# I2C_MB.net
KiCad netlist of a schematic drawn in Altium Designer
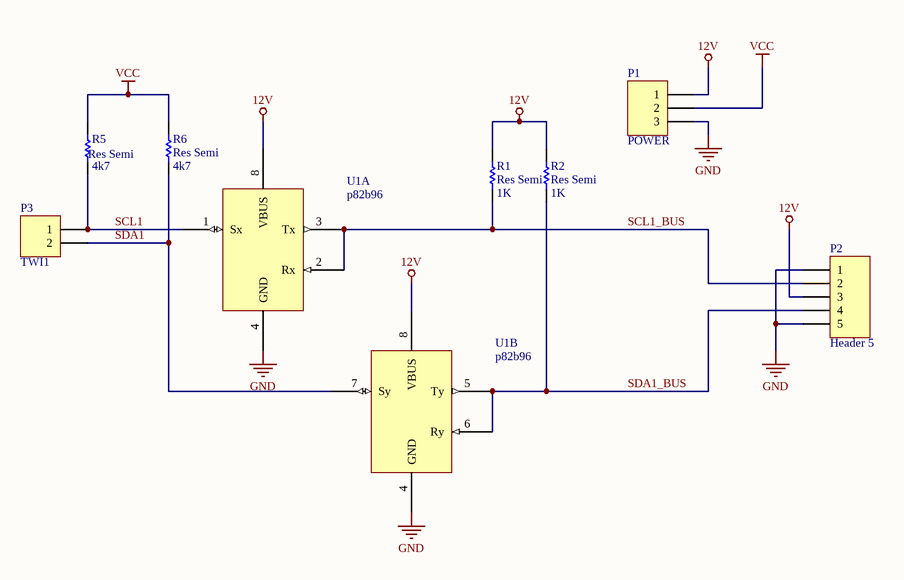
[diagram p0: I2C_MB.SchDoc]

(export (version "E")
  (design (tool "Eeschema 10.0.6"))
  (components
    (comp (ref "P1")
      (value "POWER")
      (footprint "HDR1X3")
      (description "Header, 3-Pin")
      (fields (field (name "PUBLISHER") "Altium Limited"))
      (libsource (lib "I2C_MB") (part "Header 3"))
    )
    (comp (ref "P2")
      (value "Header 5")
      (footprint "HDR1X5")
      (description "Header, 5-Pin")
      (fields (field (name "PUBLISHER") "Altium Limited"))
      (libsource (lib "Miscellaneous Connectors") (part "Header 5"))
    )
    (comp (ref "P3")
      (value "TWI1")
      (footprint "HDR1X2")
      (description "Header, 2-Pin")
      (fields (field (name "PUBLISHER") "Altium Limited"))
      (libsource (lib "I2C_MB") (part "Header 2"))
    )
    (comp (ref "R1")
      (value "Res Semi")
      (footprint "AXIAL-0.5")
      (description "Semiconductor Resistor")
      (fields (field (name "ALTIUM_VALUE") "1K") (field (name "PUBLISHER") "Altium Limited"))
      (libsource (lib "Miscellaneous Devices") (part "Res Semi"))
    )
    (comp (ref "R2")
      (value "Res Semi")
      (footprint "AXIAL-0.5")
      (description "Semiconductor Resistor")
      (fields (field (name "ALTIUM_VALUE") "1K") (field (name "PUBLISHER") "Altium Limited"))
      (libsource (lib "Miscellaneous Devices") (part "Res Semi"))
    )
    (comp (ref "R5")
      (value "Res Semi")
      (footprint "AXIAL-0.5")
      (description "Semiconductor Resistor")
      (fields (field (name "ALTIUM_VALUE") "4k7") (field (name "PUBLISHER") "Altium Limited"))
      (libsource (lib "I2C_MB") (part "Res Semi"))
    )
    (comp (ref "R6")
      (value "Res Semi")
      (footprint "AXIAL-0.5")
      (description "Semiconductor Resistor")
      (fields (field (name "ALTIUM_VALUE") "4k7") (field (name "PUBLISHER") "Altium Limited"))
      (libsource (lib "I2C_MB") (part "Res Semi"))
    )
    (comp (ref "U1") (value "p82b96") (footprint "SOIC8") (libsource (lib "I2C_MB") (part "p82b96")))
  )
  (nets
    (net (code "1") (name "/SCL1") (class "Default")
      (node (ref "P3") (pin "1") (pinfunction "1_1") (pintype "passive"))
      (node (ref "R5") (pin "1") (pinfunction "1_1") (pintype "passive"))
      (node (ref "U1") (pin "1") (pinfunction "Sx_1") (pintype "bidirectional"))
    )
    (net (code "2") (name "/SCL1_BUS") (class "Default")
      (node (ref "P2") (pin "2") (pinfunction "2_2") (pintype "passive"))
      (node (ref "R1") (pin "1") (pinfunction "1_1") (pintype "passive"))
      (node (ref "U1") (pin "2") (pinfunction "Rx_2") (pintype "input"))
      (node (ref "U1") (pin "3") (pinfunction "Tx_3") (pintype "output"))
    )
    (net (code "3") (name "/SDA1") (class "Default")
      (node (ref "P3") (pin "2") (pinfunction "2_2") (pintype "passive"))
      (node (ref "R6") (pin "1") (pinfunction "1_1") (pintype "passive"))
      (node (ref "U1") (pin "7") (pinfunction "Sy_7") (pintype "bidirectional"))
    )
    (net (code "4") (name "/SDA1_BUS") (class "Default")
      (node (ref "P2") (pin "4") (pinfunction "4_4") (pintype "passive"))
      (node (ref "R2") (pin "1") (pinfunction "1_1") (pintype "passive"))
      (node (ref "U1") (pin "5") (pinfunction "Ty_5") (pintype "output"))
      (node (ref "U1") (pin "6") (pinfunction "Ry_6") (pintype "input"))
    )
    (net (code "5") (name "12V") (class "Default")
      (node (ref "P1") (pin "1") (pinfunction "1_1") (pintype "passive"))
      (node (ref "P2") (pin "3") (pinfunction "3_3") (pintype "passive"))
      (node (ref "R1") (pin "2") (pinfunction "2_2") (pintype "passive"))
      (node (ref "R2") (pin "2") (pinfunction "2_2") (pintype "passive"))
      (node (ref "U1") (pin "8") (pinfunction "VBUS_8") (pintype "power_in"))
    )
    (net (code "6") (name "GND") (class "Default")
      (node (ref "P1") (pin "3") (pinfunction "3_3") (pintype "passive"))
      (node (ref "P2") (pin "1") (pinfunction "1_1") (pintype "passive"))
      (node (ref "P2") (pin "5") (pinfunction "5_5") (pintype "passive"))
      (node (ref "U1") (pin "4") (pinfunction "GND_4") (pintype "power_in"))
    )
    (net (code "7") (name "VCC") (class "Default")
      (node (ref "P1") (pin "2") (pinfunction "2_2") (pintype "passive"))
      (node (ref "R5") (pin "2") (pinfunction "2_2") (pintype "passive"))
      (node (ref "R6") (pin "2") (pinfunction "2_2") (pintype "passive"))
    )
  )
)
